# sensor-board.net
KiCad netlist of a schematic drawn in EAGLE
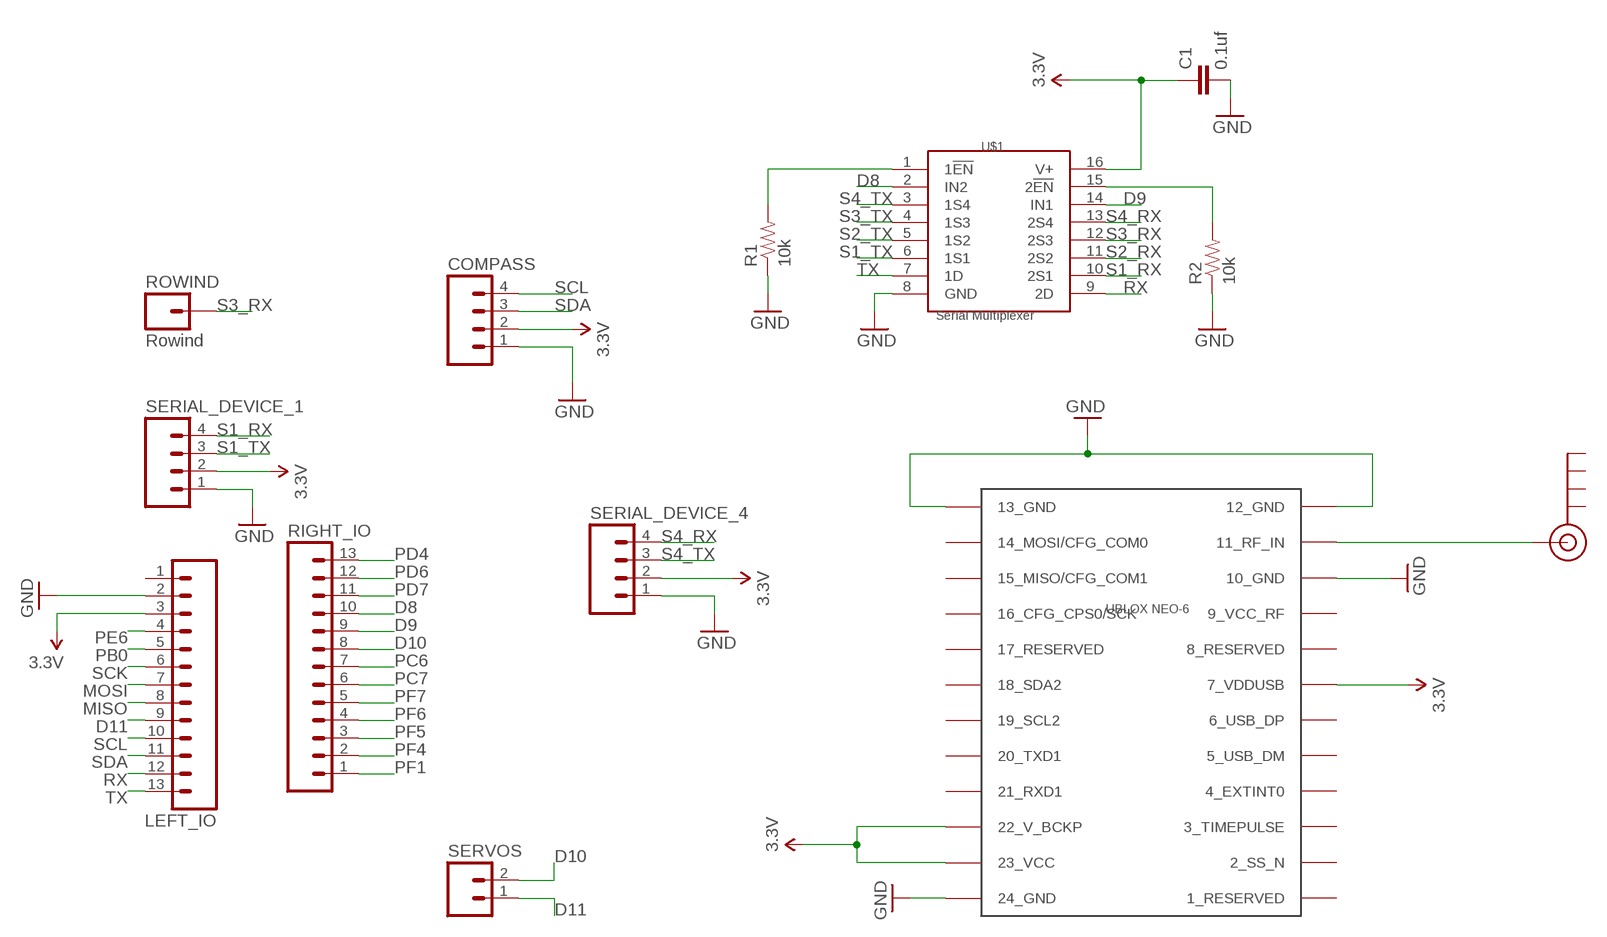
[diagram p0: schematic, sheet 1]

(export (version "E")
  (design (tool "Eeschema 10.0.6"))
  (components
    (comp (ref "C1")
      (value "0.1uf")
      (footprint "eagle-import:C0805")
      (libsource (lib "eagle-import") (part "C0805"))
    )
    (comp (ref "COMPASS")
      (value "M04PTH")
      (footprint "eagle-import:1X04")
      (libsource (lib "eagle-import") (part "M04PTH"))
    )
    (comp (ref "J$1")
      (value "SMA_EDGE")
      (footprint "eagle-import:SMA-EDGE")
      (libsource (lib "eagle-import") (part "SMA_EDGE"))
    )
    (comp (ref "LEFT_IO")
      (value "M13")
      (footprint "eagle-import:1X13")
      (libsource (lib "eagle-import") (part "M13"))
    )
    (comp (ref "R1")
      (value "10k")
      (footprint "eagle-import:AXIAL-0.3")
      (libsource (lib "eagle-import") (part "10KOHM-1/4W-1%(PTH)HORIZ"))
    )
    (comp (ref "R2")
      (value "10k")
      (footprint "eagle-import:AXIAL-0.3")
      (libsource (lib "eagle-import") (part "10KOHM-1/4W-1%(PTH)HORIZ"))
    )
    (comp (ref "RIGHT_IO")
      (value "M13")
      (footprint "eagle-import:1X13")
      (libsource (lib "eagle-import") (part "M13"))
    )
    (comp (ref "ROWIND")
      (value "Rowind")
      (footprint "eagle-import:1X01")
      (libsource (lib "eagle-import") (part "M01PTH"))
    )
    (comp (ref "SERIAL_DEVICE_1")
      (value "M04PTH")
      (footprint "eagle-import:1X04")
      (libsource (lib "eagle-import") (part "M04PTH"))
    )
    (comp (ref "SERIAL_DEVICE_4")
      (value "M04PTH")
      (footprint "eagle-import:1X04")
      (libsource (lib "eagle-import") (part "M04PTH"))
    )
    (comp (ref "SERVOS")
      (value "M02PTH")
      (footprint "eagle-import:1X02")
      (libsource (lib "eagle-import") (part "M02PTH"))
    )
    (comp (ref "U$1")
      (value "Serial Multiplexer")
      (footprint "eagle-import:16TSSOP")
      (libsource (lib "eagle-import") (part "TS3A5017"))
    )
    (comp (ref "U$2")
      (value "UBLOX_NEO-6")
      (footprint "eagle-import:UBLOX_NEO-6P")
      (libsource (lib "eagle-import") (part "UBLOX_NEO-6"))
    )
  )
  (nets
    (net (code "1") (name "/D8") (class "Default")
      (node (ref "RIGHT_IO") (pin "10") (pinfunction "10_10") (pintype "passive"))
      (node (ref "U$1") (pin "2") (pinfunction "IN2_2") (pintype "bidirectional"))
    )
    (net (code "2") (name "/D9") (class "Default")
      (node (ref "RIGHT_IO") (pin "9") (pinfunction "9_9") (pintype "passive"))
      (node (ref "U$1") (pin "14") (pinfunction "IN1_14") (pintype "bidirectional"))
    )
    (net (code "3") (name "/D10") (class "Default")
      (node (ref "RIGHT_IO") (pin "8") (pinfunction "8_8") (pintype "passive"))
      (node (ref "SERVOS") (pin "2") (pinfunction "2_2") (pintype "passive"))
    )
    (net (code "4") (name "/D11") (class "Default")
      (node (ref "LEFT_IO") (pin "9") (pinfunction "9_9") (pintype "passive"))
      (node (ref "SERVOS") (pin "1") (pinfunction "1_1") (pintype "passive"))
    )
    (net (code "5") (name "/MISO") (class "Default")
      (node (ref "LEFT_IO") (pin "8") (pinfunction "8_8") (pintype "passive"))
    )
    (net (code "6") (name "/MOSI") (class "Default")
      (node (ref "LEFT_IO") (pin "7") (pinfunction "7_7") (pintype "passive"))
    )
    (net (code "7") (name "/PB0") (class "Default")
      (node (ref "LEFT_IO") (pin "5") (pinfunction "5_5") (pintype "passive"))
    )
    (net (code "8") (name "/PC6") (class "Default")
      (node (ref "RIGHT_IO") (pin "7") (pinfunction "7_7") (pintype "passive"))
    )
    (net (code "9") (name "/PC7") (class "Default")
      (node (ref "RIGHT_IO") (pin "6") (pinfunction "6_6") (pintype "passive"))
    )
    (net (code "10") (name "/PD4") (class "Default")
      (node (ref "RIGHT_IO") (pin "13") (pinfunction "13_13") (pintype "passive"))
    )
    (net (code "11") (name "/PD6") (class "Default")
      (node (ref "RIGHT_IO") (pin "12") (pinfunction "12_12") (pintype "passive"))
    )
    (net (code "12") (name "/PD7") (class "Default")
      (node (ref "RIGHT_IO") (pin "11") (pinfunction "11_11") (pintype "passive"))
    )
    (net (code "13") (name "/PE6") (class "Default")
      (node (ref "LEFT_IO") (pin "4") (pinfunction "4_4") (pintype "passive"))
    )
    (net (code "14") (name "/PF1") (class "Default")
      (node (ref "RIGHT_IO") (pin "1") (pinfunction "1_1") (pintype "passive"))
    )
    (net (code "15") (name "/PF4") (class "Default")
      (node (ref "RIGHT_IO") (pin "2") (pinfunction "2_2") (pintype "passive"))
    )
    (net (code "16") (name "/PF5") (class "Default")
      (node (ref "RIGHT_IO") (pin "3") (pinfunction "3_3") (pintype "passive"))
    )
    (net (code "17") (name "/PF6") (class "Default")
      (node (ref "RIGHT_IO") (pin "4") (pinfunction "4_4") (pintype "passive"))
    )
    (net (code "18") (name "/PF7") (class "Default")
      (node (ref "RIGHT_IO") (pin "5") (pinfunction "5_5") (pintype "passive"))
    )
    (net (code "19") (name "/RX") (class "Default")
      (node (ref "LEFT_IO") (pin "12") (pinfunction "12_12") (pintype "passive"))
      (node (ref "U$1") (pin "9") (pinfunction "2D_9") (pintype "bidirectional"))
    )
    (net (code "20") (name "/S1_RX") (class "Default")
      (node (ref "SERIAL_DEVICE_1") (pin "4") (pinfunction "4_4") (pintype "passive"))
      (node (ref "U$1") (pin "10") (pinfunction "2S1_10") (pintype "bidirectional"))
    )
    (net (code "21") (name "/S1_TX") (class "Default")
      (node (ref "SERIAL_DEVICE_1") (pin "3") (pinfunction "3_3") (pintype "passive"))
      (node (ref "U$1") (pin "6") (pinfunction "1S1_6") (pintype "bidirectional"))
    )
    (net (code "22") (name "/S2_RX") (class "Default")
      (node (ref "U$1") (pin "11") (pinfunction "2S2_11") (pintype "bidirectional"))
    )
    (net (code "23") (name "/S2_TX") (class "Default")
      (node (ref "U$1") (pin "5") (pinfunction "1S2_5") (pintype "bidirectional"))
    )
    (net (code "24") (name "/S3_RX") (class "Default")
      (node (ref "ROWIND") (pin "1") (pinfunction "1_1") (pintype "passive"))
      (node (ref "U$1") (pin "12") (pinfunction "2S3_12") (pintype "bidirectional"))
    )
    (net (code "25") (name "/S3_TX") (class "Default")
      (node (ref "U$1") (pin "4") (pinfunction "1S3_4") (pintype "bidirectional"))
    )
    (net (code "26") (name "/S4_RX") (class "Default")
      (node (ref "SERIAL_DEVICE_4") (pin "4") (pinfunction "4_4") (pintype "passive"))
      (node (ref "U$1") (pin "13") (pinfunction "2S4_13") (pintype "bidirectional"))
    )
    (net (code "27") (name "/S4_TX") (class "Default")
      (node (ref "SERIAL_DEVICE_4") (pin "3") (pinfunction "3_3") (pintype "passive"))
      (node (ref "U$1") (pin "3") (pinfunction "1S4_3") (pintype "bidirectional"))
    )
    (net (code "28") (name "/SCK") (class "Default")
      (node (ref "LEFT_IO") (pin "6") (pinfunction "6_6") (pintype "passive"))
    )
    (net (code "29") (name "/SCL") (class "Default")
      (node (ref "COMPASS") (pin "4") (pinfunction "4_4") (pintype "passive"))
      (node (ref "LEFT_IO") (pin "10") (pinfunction "10_10") (pintype "passive"))
    )
    (net (code "30") (name "/SDA") (class "Default")
      (node (ref "COMPASS") (pin "3") (pinfunction "3_3") (pintype "passive"))
      (node (ref "LEFT_IO") (pin "11") (pinfunction "11_11") (pintype "passive"))
    )
    (net (code "31") (name "/TX") (class "Default")
      (node (ref "LEFT_IO") (pin "13") (pinfunction "13_13") (pintype "passive"))
      (node (ref "U$1") (pin "7") (pinfunction "1D_7") (pintype "bidirectional"))
    )
    (net (code "32") (name "3.3V") (class "Default")
      (node (ref "C1") (pin "1") (pinfunction "1_1") (pintype "passive"))
      (node (ref "COMPASS") (pin "2") (pinfunction "2_2") (pintype "passive"))
      (node (ref "LEFT_IO") (pin "3") (pinfunction "3_3") (pintype "passive"))
      (node (ref "SERIAL_DEVICE_1") (pin "2") (pinfunction "2_2") (pintype "passive"))
      (node (ref "SERIAL_DEVICE_4") (pin "2") (pinfunction "2_2") (pintype "passive"))
      (node (ref "U$1") (pin "16") (pinfunction "V+_16") (pintype "bidirectional"))
      (node (ref "U$2") (pin "22_V_BCKP") (pinfunction "22_V_BCKP_22_V_BCKP") (pintype "bidirectional"))
      (node (ref "U$2") (pin "23_VCC") (pinfunction "23_VCC_23_VCC") (pintype "bidirectional"))
      (node (ref "U$2") (pin "7_VDDUSB") (pinfunction "7_VDDUSB_7_VDDUSB") (pintype "bidirectional"))
    )
    (net (code "33") (name "GND") (class "Default")
      (node (ref "C1") (pin "2") (pinfunction "2_2") (pintype "passive"))
      (node (ref "COMPASS") (pin "1") (pinfunction "1_1") (pintype "passive"))
      (node (ref "LEFT_IO") (pin "2") (pinfunction "2_2") (pintype "passive"))
      (node (ref "R1") (pin "P$1") (pinfunction "1_P$1") (pintype "passive"))
      (node (ref "R2") (pin "P$1") (pinfunction "1_P$1") (pintype "passive"))
      (node (ref "SERIAL_DEVICE_1") (pin "1") (pinfunction "1_1") (pintype "passive"))
      (node (ref "SERIAL_DEVICE_4") (pin "1") (pinfunction "1_1") (pintype "passive"))
      (node (ref "U$1") (pin "8") (pinfunction "GND_8") (pintype "bidirectional"))
      (node (ref "U$2") (pin "10_GND") (pinfunction "10_GND_10_GND") (pintype "bidirectional"))
      (node (ref "U$2") (pin "12_GND") (pinfunction "12_GND_12_GND") (pintype "bidirectional"))
      (node (ref "U$2") (pin "13_GND") (pinfunction "13_GND_13_GND") (pintype "bidirectional"))
      (node (ref "U$2") (pin "24_GND") (pinfunction "24_GND_24_GND") (pintype "bidirectional"))
    )
    (net (code "34") (name "Net-(J$1-SIGNAL)") (class "Default")
      (node (ref "J$1") (pin "SIG") (pinfunction "SIGNAL_SIG") (pintype "bidirectional"))
      (node (ref "U$2") (pin "11_RF_IN") (pinfunction "11_RF_IN_11_RF_IN") (pintype "bidirectional"))
    )
    (net (code "35") (name "Net-(R1-2)") (class "Default")
      (node (ref "R1") (pin "P$2") (pinfunction "2_P$2") (pintype "passive"))
      (node (ref "U$1") (pin "1") (pinfunction "1~{EN}_1") (pintype "bidirectional"))
    )
    (net (code "36") (name "Net-(R2-2)") (class "Default")
      (node (ref "R2") (pin "P$2") (pinfunction "2_P$2") (pintype "passive"))
      (node (ref "U$1") (pin "15") (pinfunction "2~{EN}_15") (pintype "bidirectional"))
    )
    (net (code "37") (name "unconnected-(J$1-GND-PadGND@0)") (class "Default")
      (node (ref "J$1") (pin "GND@0") (pinfunction "GND_GND@0") (pintype "bidirectional"))
    )
    (net (code "38") (name "unconnected-(J$1-GND-PadGND@1)") (class "Default")
      (node (ref "J$1") (pin "GND@1") (pinfunction "GND_GND@1") (pintype "bidirectional"))
    )
    (net (code "39") (name "unconnected-(J$1-GND-PadGND@2)") (class "Default")
      (node (ref "J$1") (pin "GND@2") (pinfunction "GND_GND@2") (pintype "bidirectional"))
    )
    (net (code "40") (name "unconnected-(J$1-GND-PadGND@3)") (class "Default")
      (node (ref "J$1") (pin "GND@3") (pinfunction "GND_GND@3") (pintype "bidirectional"))
    )
    (net (code "41") (name "unconnected-(LEFT_IO-Pad1)") (class "Default")
      (node (ref "LEFT_IO") (pin "1") (pinfunction "1_1") (pintype "passive"))
    )
    (net (code "42") (name "unconnected-(U$2-Pad1_RESERVED)") (class "Default")
      (node (ref "U$2") (pin "1_RESERVED") (pinfunction "1_RESERVED_1_RESERVED") (pintype "bidirectional"))
    )
    (net (code "43") (name "unconnected-(U$2-Pad2_SS_N)") (class "Default")
      (node (ref "U$2") (pin "2_SS_N") (pinfunction "2_SS_N_2_SS_N") (pintype "bidirectional"))
    )
    (net (code "44") (name "unconnected-(U$2-Pad3_TIMEPULSE)") (class "Default")
      (node (ref "U$2") (pin "3_TIMEPULSE") (pinfunction "3_TIMEPULSE_3_TIMEPULSE") (pintype "bidirectional"))
    )
    (net (code "45") (name "unconnected-(U$2-Pad4_EXTINT0)") (class "Default")
      (node (ref "U$2") (pin "4_EXTINT0") (pinfunction "4_EXTINT0_4_EXTINT0") (pintype "bidirectional"))
    )
    (net (code "46") (name "unconnected-(U$2-Pad5_USB_DM)") (class "Default")
      (node (ref "U$2") (pin "5_USB_DM") (pinfunction "5_USB_DM_5_USB_DM") (pintype "bidirectional"))
    )
    (net (code "47") (name "unconnected-(U$2-Pad6_USB_DP)") (class "Default")
      (node (ref "U$2") (pin "6_USB_DP") (pinfunction "6_USB_DP_6_USB_DP") (pintype "bidirectional"))
    )
    (net (code "48") (name "unconnected-(U$2-Pad8_RESERVED)") (class "Default")
      (node (ref "U$2") (pin "8_RESERVED") (pinfunction "8_RESERVED_8_RESERVED") (pintype "bidirectional"))
    )
    (net (code "49") (name "unconnected-(U$2-Pad9_VCC_RF)") (class "Default")
      (node (ref "U$2") (pin "9_VCC_RF") (pinfunction "9_VCC_RF_9_VCC_RF") (pintype "bidirectional"))
    )
    (net (code "50") (name "unconnected-(U$2-Pad14_MOSI{slash}CFG_COM0)") (class "Default")
      (node (ref "U$2") (pin "14_MOSI/CFG_COM0") (pinfunction "14_MOSI/CFG_COM0_14_MOSI/CFG_COM0") (pintype "bidirectional"))
    )
    (net (code "51") (name "unconnected-(U$2-Pad15_MISO{slash}CFG_COM1)") (class "Default")
      (node (ref "U$2") (pin "15_MISO/CFG_COM1") (pinfunction "15_MISO/CFG_COM1_15_MISO/CFG_COM1") (pintype "bidirectional"))
    )
    (net (code "52") (name "unconnected-(U$2-Pad16_CFG_CPS0{slash}SCK)") (class "Default")
      (node (ref "U$2") (pin "16_CFG_CPS0/SCK") (pinfunction "16_CFG_CPS0/SCK_16_CFG_CPS0/SCK") (pintype "bidirectional"))
    )
    (net (code "53") (name "unconnected-(U$2-Pad17_RESERVED)") (class "Default")
      (node (ref "U$2") (pin "17_RESERVED") (pinfunction "17_RESERVED_17_RESERVED") (pintype "bidirectional"))
    )
    (net (code "54") (name "unconnected-(U$2-Pad18_SDA2)") (class "Default")
      (node (ref "U$2") (pin "18_SDA2") (pinfunction "18_SDA2_18_SDA2") (pintype "bidirectional"))
    )
    (net (code "55") (name "unconnected-(U$2-Pad19_SCL2)") (class "Default")
      (node (ref "U$2") (pin "19_SCL2") (pinfunction "19_SCL2_19_SCL2") (pintype "bidirectional"))
    )
    (net (code "56") (name "unconnected-(U$2-Pad20_TXD1)") (class "Default")
      (node (ref "U$2") (pin "20_TXD1") (pinfunction "20_TXD1_20_TXD1") (pintype "bidirectional"))
    )
    (net (code "57") (name "unconnected-(U$2-Pad21_RXD1)") (class "Default")
      (node (ref "U$2") (pin "21_RXD1") (pinfunction "21_RXD1_21_RXD1") (pintype "bidirectional"))
    )
  )
)
